# SCH_nfcbusinesscard2_2025-07-16.net
KiCad netlist of a schematic drawn in EasyEDA
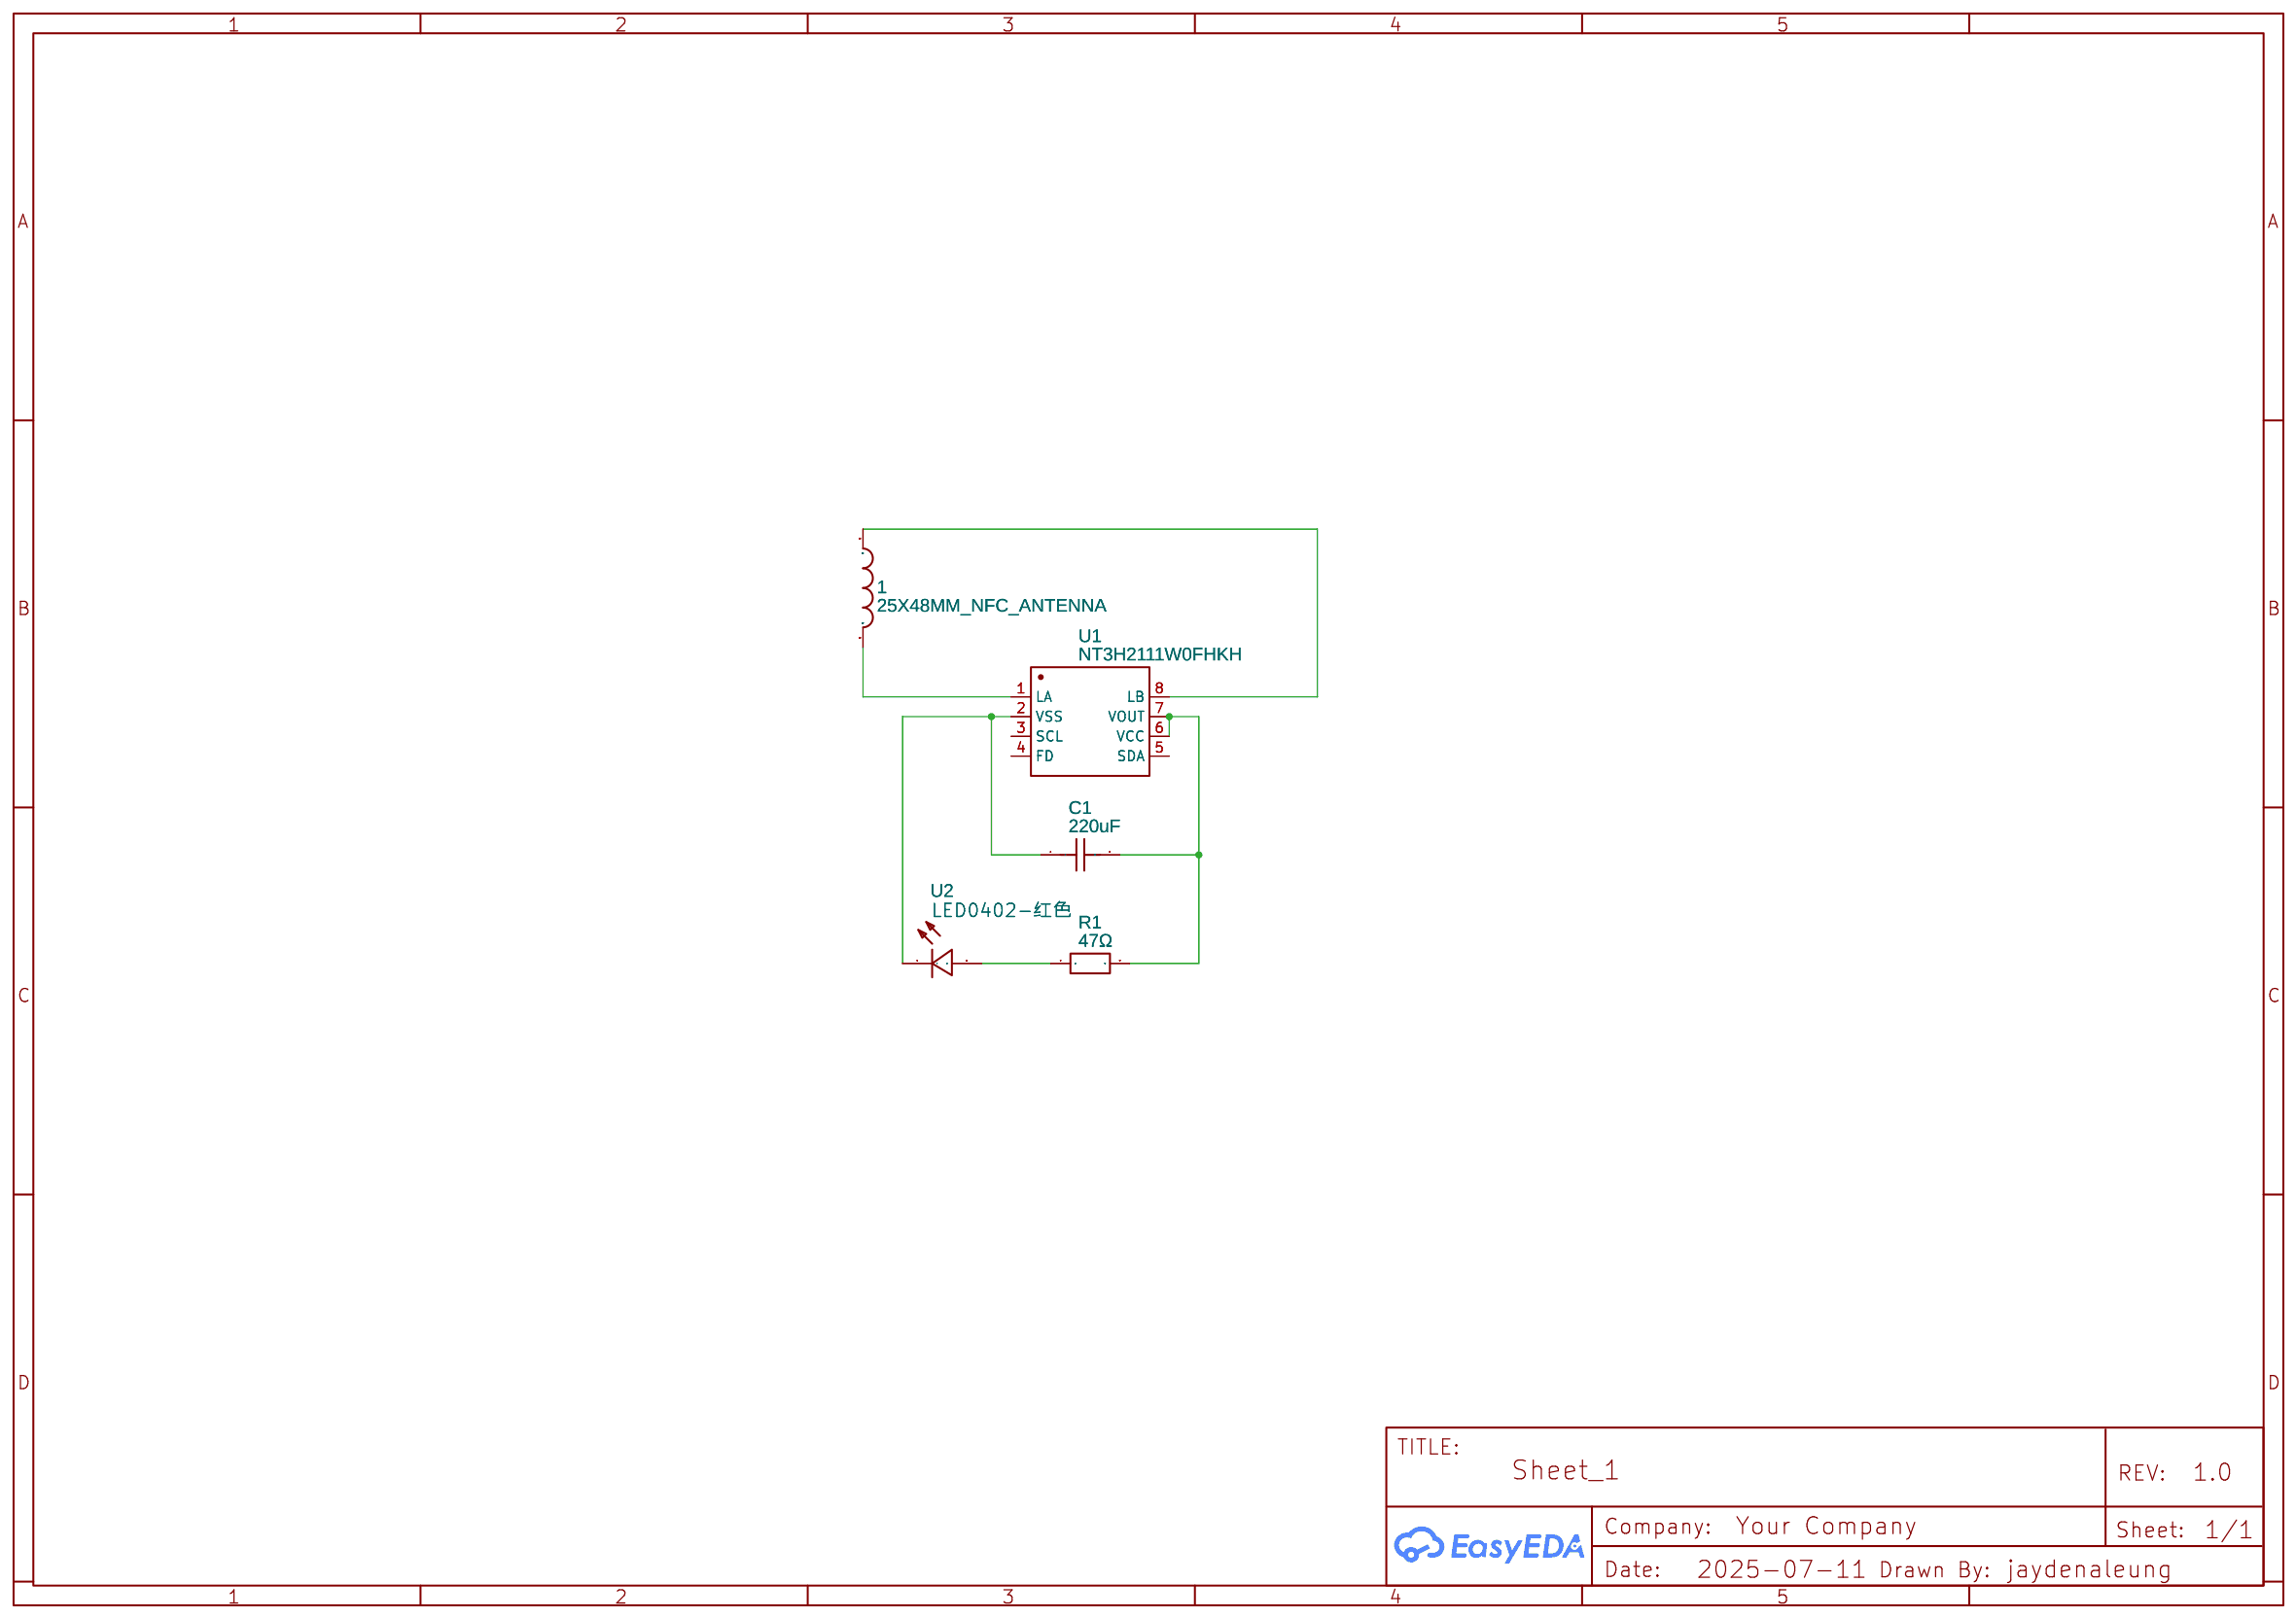
[diagram p0: schematic sheet]

(export (version "E")
  (design (tool "Eeschema 10.0.6"))
  (components
    (comp (ref "1") (value "25X48MM_NFC_ANTENNA") (libsource (lib "") (part "25X48MM_NFC_ANTENNA")))
    (comp (ref "C1") (value "220uF") (libsource (lib "") (part "C_0603_US")))
    (comp (ref "R1") (value "47Ω") (libsource (lib "") (part "R_0603_EU")))
    (comp (ref "U1")
      (value "NT3H2111W0FHKH")
      (fields (field (name "Manufacturer") "NXP(恩智浦)"))
      (libsource (lib "") (part "NT3H2111W0FHKH"))
    )
    (comp (ref "U2") (value "LED0402-红色") (libsource (lib "") (part "LED0402-红色")))
  )
  (nets
    (net (code "1") (name "Net-(U1-LA)") (class "Default")
      (node (ref "1") (pin "P$2") (pinfunction "P$2_P$2") (pintype "bidirectional"))
      (node (ref "U1") (pin "1") (pinfunction "LA_1") (pintype "unspecified"))
    )
    (net (code "2") (name "Net-(U1-LB)") (class "Default")
      (node (ref "1") (pin "P$1") (pinfunction "P$1_P$1") (pintype "bidirectional"))
      (node (ref "U1") (pin "8") (pinfunction "LB_8") (pintype "unspecified"))
    )
    (net (code "3") (name "Net-(U1-VCC)") (class "Default")
      (node (ref "C1") (pin "2") (pinfunction "2_2") (pintype "unspecified"))
      (node (ref "R1") (pin "2") (pinfunction "2_2") (pintype "unspecified"))
      (node (ref "U1") (pin "6") (pinfunction "VCC_6") (pintype "unspecified"))
      (node (ref "U1") (pin "7") (pinfunction "VOUT_7") (pintype "unspecified"))
    )
    (net (code "4") (name "Net-(U1-VSS)") (class "Default")
      (node (ref "C1") (pin "1") (pinfunction "1_1") (pintype "unspecified"))
      (node (ref "U1") (pin "2") (pinfunction "VSS_2") (pintype "unspecified"))
      (node (ref "U2") (pin "1") (pinfunction "-_1") (pintype "unspecified"))
    )
    (net (code "5") (name "Net-(U2-+)") (class "Default")
      (node (ref "R1") (pin "1") (pinfunction "1_1") (pintype "unspecified"))
      (node (ref "U2") (pin "2") (pinfunction "+_2") (pintype "unspecified"))
    )
    (net (code "6") (name "unconnected-(U1-FD-Pad4)") (class "Default")
      (node (ref "U1") (pin "4") (pinfunction "FD_4") (pintype "unspecified"))
    )
    (net (code "7") (name "unconnected-(U1-SCL-Pad3)") (class "Default")
      (node (ref "U1") (pin "3") (pinfunction "SCL_3") (pintype "unspecified"))
    )
    (net (code "8") (name "unconnected-(U1-SDA-Pad5)") (class "Default")
      (node (ref "U1") (pin "5") (pinfunction "SDA_5") (pintype "unspecified"))
    )
  )
)
